# connector_3v3.net
KiCad netlist of a schematic drawn in Altium Designer
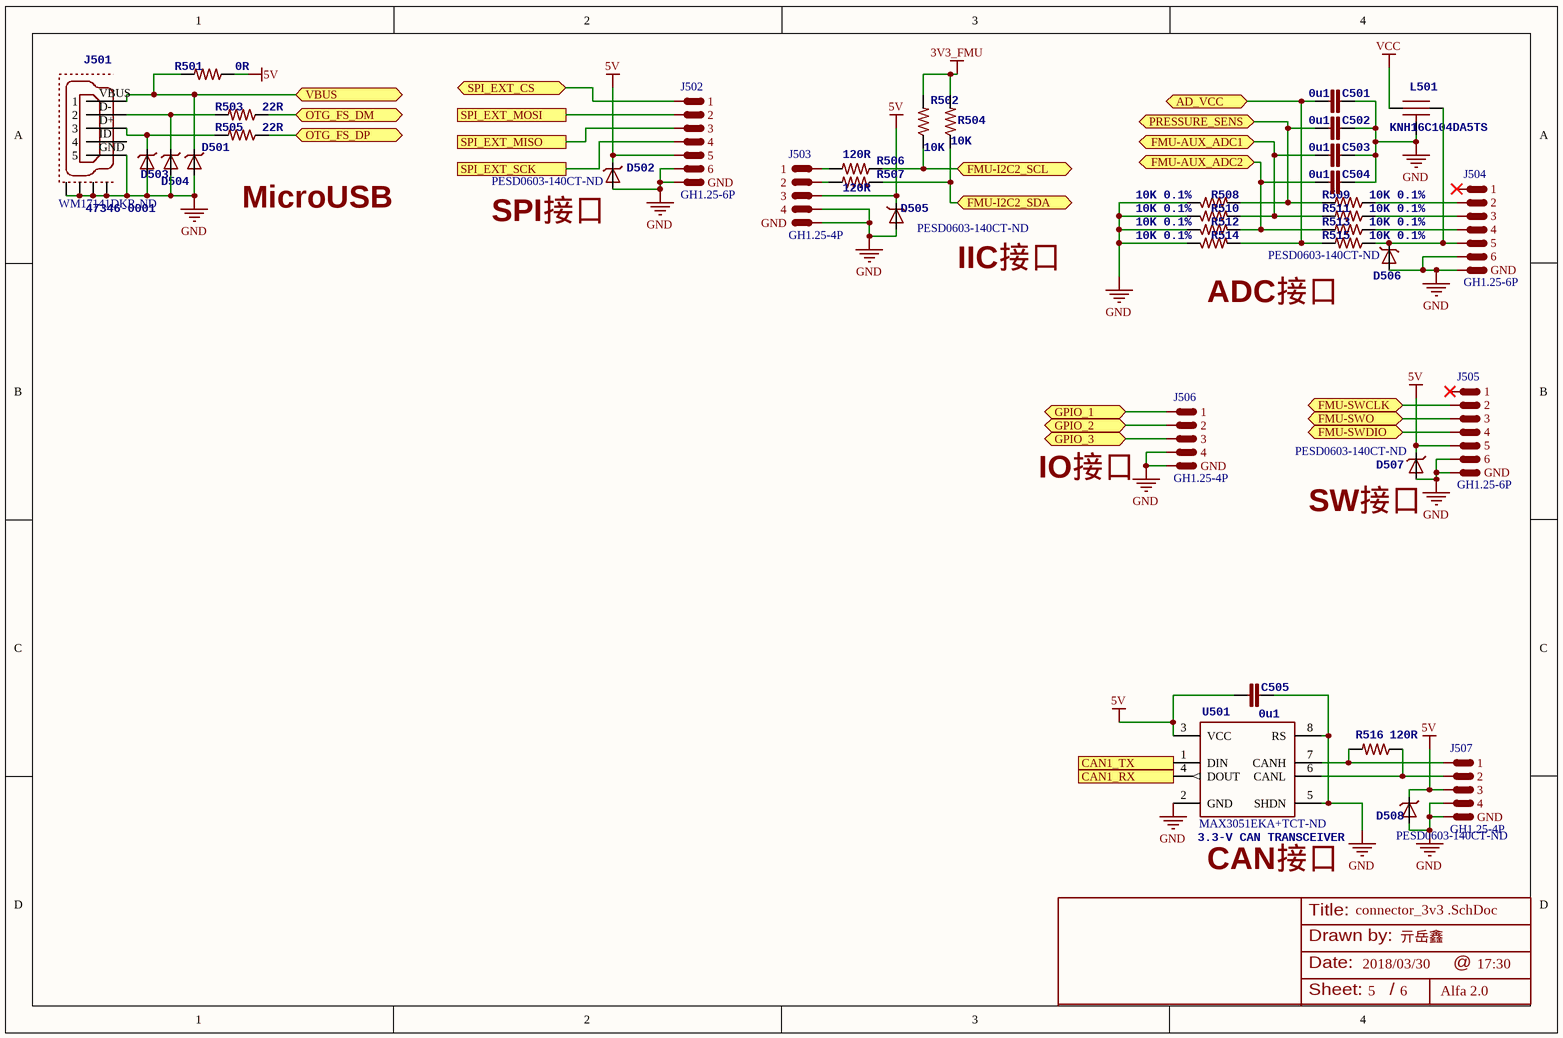
[diagram p0: connector_3v3 .SchDoc]

(export (version "E")
  (design (tool "Eeschema 10.0.6"))
  (components
    (comp (ref "C501")
      (value "0u1")
      (footprint "0603-CAP")
      (description "Capacitor, 0.1uF, 16V, Y5V, 0402, Ceramic")
      (fields (field (name "PARTNO") "CC0402ZRY5V7BB104") (field (name "3DR_PARTNO") "ECM0700"))
      (libsource (lib "Q's无源元件类") (part "CAP0603-0.1uF"))
    )
    (comp (ref "C502")
      (value "0u1")
      (footprint "0603-CAP")
      (description "Capacitor, 0.1uF, 16V, Y5V, 0402, Ceramic")
      (fields (field (name "PARTNO") "CC0402ZRY5V7BB104") (field (name "3DR_PARTNO") "ECM0700"))
      (libsource (lib "Q's无源元件类") (part "CAP0603-0.1uF"))
    )
    (comp (ref "C503")
      (value "0u1")
      (footprint "0603-CAP")
      (description "Capacitor, 0.1uF, 16V, Y5V, 0402, Ceramic")
      (fields (field (name "PARTNO") "CC0402ZRY5V7BB104") (field (name "3DR_PARTNO") "ECM0700"))
      (libsource (lib "Q's无源元件类") (part "CAP0603-0.1uF"))
    )
    (comp (ref "C504")
      (value "0u1")
      (footprint "0603-CAP")
      (description "Capacitor, 0.1uF, 16V, Y5V, 0402, Ceramic")
      (fields (field (name "PARTNO") "CC0402ZRY5V7BB104") (field (name "3DR_PARTNO") "ECM0700"))
      (libsource (lib "Q's无源元件类") (part "CAP0603-0.1uF"))
    )
    (comp (ref "C505")
      (value "0u1")
      (footprint "0603-CAP")
      (description "Capacitor, 0.1uF, 16V, Y5V, 0402, Ceramic")
      (fields (field (name "PARTNO") "CC0402ZRY5V7BB104") (field (name "3DR_PARTNO") "ECM0700"))
      (libsource (lib "Q's无源元件类") (part "CAP0603-0.1uF"))
    )
    (comp (ref "D501")
      (value "PESD0603-140")
      (footprint "0603-ESD")
      (description "TVS DIODE 14V 0603")
      (libsource (lib "Q's无源元件类") (part "DIODE-ESD"))
    )
    (comp (ref "D502")
      (value "PESD0603-140")
      (footprint "0603-ESD")
      (description "TVS DIODE 14V 0603")
      (fields (field (name "SUPPLIER PART NUMBER 1") "PESD0603-140CT-ND"))
      (libsource (lib "Q's无源元件类") (part "DIODE-ESD"))
    )
    (comp (ref "D503")
      (value "PESD0603-140")
      (footprint "0603-ESD")
      (description "TVS DIODE 14V 0603")
      (libsource (lib "Q's无源元件类") (part "DIODE-ESD"))
    )
    (comp (ref "D504")
      (value "PESD0603-140")
      (footprint "0603-ESD")
      (description "TVS DIODE 14V 0603")
      (libsource (lib "Q's无源元件类") (part "DIODE-ESD"))
    )
    (comp (ref "D505")
      (value "PESD0603-140")
      (footprint "0603-ESD")
      (description "TVS DIODE 14V 0603")
      (fields (field (name "SUPPLIER PART NUMBER 1") "PESD0603-140CT-ND"))
      (libsource (lib "Q's无源元件类") (part "DIODE-ESD"))
    )
    (comp (ref "D506")
      (value "PESD0603-140")
      (footprint "0603-ESD")
      (description "TVS DIODE 14V 0603")
      (fields (field (name "SUPPLIER PART NUMBER 1") "PESD0603-140CT-ND"))
      (libsource (lib "Q's无源元件类") (part "DIODE-ESD"))
    )
    (comp (ref "D507")
      (value "PESD0603-140")
      (footprint "0603-ESD")
      (description "TVS DIODE 14V 0603")
      (fields (field (name "SUPPLIER PART NUMBER 1") "PESD0603-140CT-ND"))
      (libsource (lib "Q's无源元件类") (part "DIODE-ESD"))
    )
    (comp (ref "D508")
      (value "PESD0603-140")
      (footprint "0603-ESD")
      (description "TVS DIODE 14V 0603")
      (fields (field (name "SUPPLIER PART NUMBER 1") "PESD0603-140CT-ND"))
      (libsource (lib "Q's无源元件类") (part "DIODE-ESD"))
    )
    (comp (ref "J501")
      (value "47346-0001")
      (footprint "MOLEX-47346-0001")
      (description "MICRO USB B, BOTTOM MOUNT")
      (fields
        (field (name "3DR_PARTNO") "ECM0486")
        (field (name "PARTNO") "0473460001")
        (field (name "SUPPLIER PART NUMBER 1") "WM17141DKR-ND")
      )
      (libsource (lib "Q's端子及图标") (part "MicroUSB"))
    )
    (comp (ref "J502")
      (value "GH1.25-6P")
      (footprint "1.25-6P")
      (description "GH1.25mm 立贴 间距1.25mm 连接器贴片")
      (libsource (lib "Q's端子及图标") (part "GH1.25-6P"))
    )
    (comp (ref "J503")
      (value "GH1.25-4P")
      (footprint "1.25-4P")
      (description "GH1.25mm 立贴 间距1.25mm 连接器贴片")
      (libsource (lib "Q's端子及图标") (part "GH1.25-4P"))
    )
    (comp (ref "J504")
      (value "GH1.25-6P")
      (footprint "1.25-6P")
      (description "GH1.25mm 立贴 间距1.25mm 连接器贴片")
      (libsource (lib "Q's端子及图标") (part "GH1.25-6P"))
    )
    (comp (ref "J505")
      (value "GH1.25-6P")
      (footprint "1.25-6P")
      (description "GH1.25mm 立贴 间距1.25mm 连接器贴片")
      (libsource (lib "Q's端子及图标") (part "GH1.25-6P"))
    )
    (comp (ref "J506")
      (value "GH1.25-4P")
      (footprint "1.25-4P")
      (description "GH1.25mm 立贴 间距1.25mm 连接器贴片")
      (libsource (lib "Q's端子及图标") (part "GH1.25-4P"))
    )
    (comp (ref "J507")
      (value "GH1.25-4P")
      (footprint "1.25-4P")
      (description "GH1.25mm 立贴 间距1.25mm 连接器贴片")
      (libsource (lib "Q's端子及图标") (part "GH1.25-4P"))
    )
    (comp (ref "L501")
      (value "KNH16C104DA5TS")
      (footprint "0603-KNH16-DA")
      (description "EMI FILTER CAP 0.1UF 2A 25V 0603")
      (fields (field (name "3DR_PARTNO") "ECM0719"))
      (libsource (lib "Q's无源元件类") (part "EMI Filters"))
    )
    (comp (ref "R501")
      (value "0R")
      (footprint "0603-RES")
      (description "RES 0R OHM 1/10W 5% 0603")
      (libsource (lib "Q's无源元件类") (part "RES0603-0R"))
    )
    (comp (ref "R502")
      (value "10K")
      (footprint "0603-RES")
      (description "RES 10K OHM 1/10W 5% 0603")
      (libsource (lib "Q's无源元件类") (part "RES0603-10K"))
    )
    (comp (ref "R503")
      (value "22R")
      (footprint "0603-RES")
      (description "RES 22R OHM 1/10W 5% 0603")
      (libsource (lib "Q's无源元件类") (part "RES0603-22R"))
    )
    (comp (ref "R504")
      (value "10K")
      (footprint "0603-RES")
      (description "RES 10K OHM 1/10W 5% 0603")
      (libsource (lib "Q's无源元件类") (part "RES0603-10K"))
    )
    (comp (ref "R505")
      (value "22R")
      (footprint "0603-RES")
      (description "RES 22R OHM 1/10W 5% 0603")
      (libsource (lib "Q's无源元件类") (part "RES0603-22R"))
    )
    (comp (ref "R506")
      (value "120R")
      (footprint "0603-RES")
      (description "RES 120R OHM 1/10W 5% 0603")
      (libsource (lib "Q's无源元件类") (part "RES0603-120R"))
    )
    (comp (ref "R507")
      (value "120R")
      (footprint "0603-RES")
      (description "RES 120R OHM 1/10W 5% 0603")
      (libsource (lib "Q's无源元件类") (part "RES0603-120R"))
    )
    (comp (ref "R508")
      (value "10K 0.1%")
      (footprint "0603-RES")
      (description "RES 10 OHM 1/10W 0.1% 0603")
      (libsource (lib "Q's无源元件类") (part "RES0603-10k_0.1%"))
    )
    (comp (ref "R509")
      (value "10K 0.1%")
      (footprint "0603-RES")
      (description "RES 10 OHM 1/10W 0.1% 0603")
      (libsource (lib "Q's无源元件类") (part "RES0603-10k_0.1%"))
    )
    (comp (ref "R510")
      (value "10K 0.1%")
      (footprint "0603-RES")
      (description "RES 10 OHM 1/10W 0.1% 0603")
      (libsource (lib "Q's无源元件类") (part "RES0603-10k_0.1%"))
    )
    (comp (ref "R511")
      (value "10K 0.1%")
      (footprint "0603-RES")
      (description "RES 10 OHM 1/10W 0.1% 0603")
      (libsource (lib "Q's无源元件类") (part "RES0603-10k_0.1%"))
    )
    (comp (ref "R512")
      (value "10K 0.1%")
      (footprint "0603-RES")
      (description "RES 10 OHM 1/10W 0.1% 0603")
      (libsource (lib "Q's无源元件类") (part "RES0603-10k_0.1%"))
    )
    (comp (ref "R513")
      (value "10K 0.1%")
      (footprint "0603-RES")
      (description "RES 10 OHM 1/10W 0.1% 0603")
      (libsource (lib "Q's无源元件类") (part "RES0603-10k_0.1%"))
    )
    (comp (ref "R514")
      (value "10K 0.1%")
      (footprint "0603-RES")
      (description "RES 10 OHM 1/10W 0.1% 0603")
      (libsource (lib "Q's无源元件类") (part "RES0603-10k_0.1%"))
    )
    (comp (ref "R515")
      (value "10K 0.1%")
      (footprint "0603-RES")
      (description "RES 10 OHM 1/10W 0.1% 0603")
      (libsource (lib "Q's无源元件类") (part "RES0603-10k_0.1%"))
    )
    (comp (ref "R516")
      (value "120R")
      (footprint "0603-RES")
      (description "RES 120R OHM 1/10W 5% 0603")
      (libsource (lib "Q's无源元件类") (part "RES0603-120R"))
    )
    (comp (ref "U501")
      (value "3.3-V CAN TRANSCEIVER")
      (footprint "SOT23-8")
      (description "IC TXRX CAN 1MBPS SOT23-8")
      (fields
        (field (name "3DR_PARTNO") "ECM0831")
        (field (name "PARTNO") "MAX3051EKA+T")
        (field (name "SUPPLIER PART NUMBER 1") "MAX3051EKA+TCT-ND")
      )
      (libsource (lib "Q's有源芯片类") (part "MAX3051"))
    )
  )
  (nets
    (net (code "1") (name "/AD_VCC") (class "Default")
      (node (ref "C501") (pin "P$1") (pinfunction "1_P$1") (pintype "passive"))
      (node (ref "R514") (pin "2") (pinfunction "2_2") (pintype "passive"))
      (node (ref "R515") (pin "2") (pinfunction "2_2") (pintype "passive"))
    )
    (net (code "2") (name "/CAN1_RX") (class "Default")
      (node (ref "U501") (pin "4") (pinfunction "DOUT_4") (pintype "output"))
    )
    (net (code "3") (name "/CAN1_TX") (class "Default")
      (node (ref "U501") (pin "1") (pinfunction "DIN_1") (pintype "passive"))
    )
    (net (code "4") (name "/FMU-AUX_ADC1") (class "Default")
      (node (ref "C503") (pin "P$1") (pinfunction "1_P$1") (pintype "passive"))
      (node (ref "R510") (pin "2") (pinfunction "2_2") (pintype "passive"))
      (node (ref "R511") (pin "2") (pinfunction "2_2") (pintype "passive"))
    )
    (net (code "5") (name "/FMU-AUX_ADC2") (class "Default")
      (node (ref "C504") (pin "P$1") (pinfunction "1_P$1") (pintype "passive"))
      (node (ref "R512") (pin "2") (pinfunction "2_2") (pintype "passive"))
      (node (ref "R513") (pin "2") (pinfunction "2_2") (pintype "passive"))
    )
    (net (code "6") (name "/FMU-I2C2_SCL") (class "Default")
      (node (ref "R502") (pin "1") (pinfunction "1_1") (pintype "passive"))
      (node (ref "R506") (pin "1") (pinfunction "1_1") (pintype "passive"))
    )
    (net (code "7") (name "/FMU-I2C2_SDA") (class "Default")
      (node (ref "R504") (pin "1") (pinfunction "1_1") (pintype "passive"))
      (node (ref "R507") (pin "1") (pinfunction "1_1") (pintype "passive"))
    )
    (net (code "8") (name "/FMU-SWCLK") (class "Default")
      (node (ref "J505") (pin "2") (pinfunction "2_2") (pintype "passive"))
    )
    (net (code "9") (name "/FMU-SWDIO") (class "Default")
      (node (ref "J505") (pin "4") (pinfunction "4_4") (pintype "passive"))
    )
    (net (code "10") (name "/FMU-SWO") (class "Default")
      (node (ref "J505") (pin "3") (pinfunction "3_3") (pintype "passive"))
    )
    (net (code "11") (name "/GPIO_1") (class "Default")
      (node (ref "J506") (pin "1") (pinfunction "1_1") (pintype "passive"))
    )
    (net (code "12") (name "/GPIO_2") (class "Default")
      (node (ref "J506") (pin "2") (pinfunction "2_2") (pintype "passive"))
    )
    (net (code "13") (name "/GPIO_3") (class "Default")
      (node (ref "J506") (pin "3") (pinfunction "3_3") (pintype "passive"))
    )
    (net (code "14") (name "/OTG_FS_DM") (class "Default")
      (node (ref "R503") (pin "1") (pinfunction "1_1") (pintype "passive"))
    )
    (net (code "15") (name "/OTG_FS_DP") (class "Default")
      (node (ref "R505") (pin "1") (pinfunction "1_1") (pintype "passive"))
    )
    (net (code "16") (name "/PRESSURE_SENS") (class "Default")
      (node (ref "C502") (pin "P$1") (pinfunction "1_P$1") (pintype "passive"))
      (node (ref "R508") (pin "2") (pinfunction "2_2") (pintype "passive"))
      (node (ref "R509") (pin "2") (pinfunction "2_2") (pintype "passive"))
    )
    (net (code "17") (name "/SPI_EXT_CS") (class "Default")
      (node (ref "J502") (pin "1") (pinfunction "1_1") (pintype "passive"))
    )
    (net (code "18") (name "/SPI_EXT_MISO") (class "Default")
      (node (ref "J502") (pin "3") (pinfunction "3_3") (pintype "passive"))
    )
    (net (code "19") (name "/SPI_EXT_MOSI") (class "Default")
      (node (ref "J502") (pin "2") (pinfunction "2_2") (pintype "passive"))
    )
    (net (code "20") (name "/SPI_EXT_SCK") (class "Default")
      (node (ref "J502") (pin "4") (pinfunction "4_4") (pintype "passive"))
    )
    (net (code "21") (name "/VBUS") (class "Default")
      (node (ref "D501") (pin "C") (pinfunction "C_C") (pintype "passive"))
      (node (ref "J501") (pin "VBUS") (pinfunction "1_VBUS") (pintype "open_emitter"))
      (node (ref "R501") (pin "2") (pinfunction "2_2") (pintype "passive"))
    )
    (net (code "22") (name "3V3_FMU") (class "Default")
      (node (ref "R502") (pin "2") (pinfunction "2_2") (pintype "passive"))
      (node (ref "R504") (pin "2") (pinfunction "2_2") (pintype "passive"))
    )
    (net (code "23") (name "5V") (class "Default")
      (node (ref "C505") (pin "P$1") (pinfunction "1_P$1") (pintype "passive"))
      (node (ref "D502") (pin "C") (pinfunction "C_C") (pintype "passive"))
      (node (ref "D505") (pin "C") (pinfunction "C_C") (pintype "passive"))
      (node (ref "D507") (pin "C") (pinfunction "C_C") (pintype "passive"))
      (node (ref "D508") (pin "C") (pinfunction "C_C") (pintype "passive"))
      (node (ref "J502") (pin "5") (pinfunction "5_5") (pintype "passive"))
      (node (ref "J503") (pin "3") (pinfunction "3_3") (pintype "passive"))
      (node (ref "J505") (pin "5") (pinfunction "5_5") (pintype "passive"))
      (node (ref "J507") (pin "3") (pinfunction "3_3") (pintype "passive"))
      (node (ref "R501") (pin "1") (pinfunction "1_1") (pintype "passive"))
      (node (ref "U501") (pin "3") (pinfunction "VCC_3") (pintype "passive"))
    )
    (net (code "24") (name "GND") (class "Default")
      (node (ref "C501") (pin "P$2") (pinfunction "2_P$2") (pintype "passive"))
      (node (ref "C502") (pin "P$2") (pinfunction "2_P$2") (pintype "passive"))
      (node (ref "C503") (pin "P$2") (pinfunction "2_P$2") (pintype "passive"))
      (node (ref "C504") (pin "P$2") (pinfunction "2_P$2") (pintype "passive"))
      (node (ref "C505") (pin "P$2") (pinfunction "2_P$2") (pintype "passive"))
      (node (ref "D501") (pin "A") (pinfunction "A_A") (pintype "passive"))
      (node (ref "D502") (pin "A") (pinfunction "A_A") (pintype "passive"))
      (node (ref "D503") (pin "A") (pinfunction "A_A") (pintype "passive"))
      (node (ref "D504") (pin "A") (pinfunction "A_A") (pintype "passive"))
      (node (ref "D505") (pin "A") (pinfunction "A_A") (pintype "passive"))
      (node (ref "D506") (pin "A") (pinfunction "A_A") (pintype "passive"))
      (node (ref "D507") (pin "A") (pinfunction "A_A") (pintype "passive"))
      (node (ref "D508") (pin "A") (pinfunction "A_A") (pintype "passive"))
      (node (ref "J501") (pin "GND") (pinfunction "5_GND") (pintype "passive"))
      (node (ref "J501") (pin "GND1") (pinfunction "GND1_GND1") (pintype "passive"))
      (node (ref "J501") (pin "GND2") (pinfunction "GND2_GND2") (pintype "passive"))
      (node (ref "J501") (pin "GND3") (pinfunction "GND3_GND3") (pintype "passive"))
      (node (ref "J501") (pin "GND4") (pinfunction "GND4_GND4") (pintype "passive"))
      (node (ref "J502") (pin "6") (pinfunction "6_6") (pintype "passive"))
      (node (ref "J502") (pin "GND") (pinfunction "GND_GND") (pintype "passive"))
      (node (ref "J503") (pin "4") (pinfunction "4_4") (pintype "passive"))
      (node (ref "J503") (pin "GND") (pinfunction "GND_GND") (pintype "passive"))
      (node (ref "J504") (pin "6") (pinfunction "6_6") (pintype "passive"))
      (node (ref "J504") (pin "GND") (pinfunction "GND_GND") (pintype "passive"))
      (node (ref "J505") (pin "6") (pinfunction "6_6") (pintype "passive"))
      (node (ref "J505") (pin "GND") (pinfunction "GND_GND") (pintype "passive"))
      (node (ref "J506") (pin "4") (pinfunction "4_4") (pintype "passive"))
      (node (ref "J506") (pin "GND") (pinfunction "GND_GND") (pintype "passive"))
      (node (ref "J507") (pin "4") (pinfunction "4_4") (pintype "passive"))
      (node (ref "J507") (pin "GND") (pinfunction "GND_GND") (pintype "passive"))
      (node (ref "L501") (pin "GND") (pinfunction "GND_GND") (pintype "passive"))
      (node (ref "R508") (pin "1") (pinfunction "1_1") (pintype "passive"))
      (node (ref "R510") (pin "1") (pinfunction "1_1") (pintype "passive"))
      (node (ref "R512") (pin "1") (pinfunction "1_1") (pintype "passive"))
      (node (ref "R514") (pin "1") (pinfunction "1_1") (pintype "passive"))
      (node (ref "U501") (pin "2") (pinfunction "GND_2") (pintype "power_in"))
      (node (ref "U501") (pin "5") (pinfunction "SHDN_5") (pintype "passive"))
      (node (ref "U501") (pin "8") (pinfunction "RS_8") (pintype "passive"))
    )
    (net (code "25") (name "Net-(D506-PadC)") (class "Default")
      (node (ref "D506") (pin "C") (pinfunction "C_C") (pintype "passive"))
      (node (ref "J504") (pin "5") (pinfunction "5_5") (pintype "passive"))
      (node (ref "L501") (pin "P$2") (pinfunction "P$2_P$2") (pintype "passive"))
      (node (ref "R515") (pin "1") (pinfunction "1_1") (pintype "passive"))
    )
    (net (code "26") (name "Net-(J501-2)") (class "Default")
      (node (ref "D504") (pin "C") (pinfunction "C_C") (pintype "passive"))
      (node (ref "J501") (pin "D-") (pinfunction "2_D-") (pintype "passive"))
      (node (ref "R503") (pin "2") (pinfunction "2_2") (pintype "passive"))
    )
    (net (code "27") (name "Net-(J501-3)") (class "Default")
      (node (ref "D503") (pin "C") (pinfunction "C_C") (pintype "passive"))
      (node (ref "J501") (pin "D+") (pinfunction "3_D+") (pintype "passive"))
      (node (ref "R505") (pin "2") (pinfunction "2_2") (pintype "passive"))
    )
    (net (code "28") (name "Net-(J503-Pad1)") (class "Default")
      (node (ref "J503") (pin "1") (pinfunction "1_1") (pintype "passive"))
      (node (ref "R506") (pin "2") (pinfunction "2_2") (pintype "passive"))
    )
    (net (code "29") (name "Net-(J503-Pad2)") (class "Default")
      (node (ref "J503") (pin "2") (pinfunction "2_2") (pintype "passive"))
      (node (ref "R507") (pin "2") (pinfunction "2_2") (pintype "passive"))
    )
    (net (code "30") (name "Net-(J504-Pad2)") (class "Default")
      (node (ref "J504") (pin "2") (pinfunction "2_2") (pintype "passive"))
      (node (ref "R509") (pin "1") (pinfunction "1_1") (pintype "passive"))
    )
    (net (code "31") (name "Net-(J504-Pad3)") (class "Default")
      (node (ref "J504") (pin "3") (pinfunction "3_3") (pintype "passive"))
      (node (ref "R511") (pin "1") (pinfunction "1_1") (pintype "passive"))
    )
    (net (code "32") (name "Net-(J504-Pad4)") (class "Default")
      (node (ref "J504") (pin "4") (pinfunction "4_4") (pintype "passive"))
      (node (ref "R513") (pin "1") (pinfunction "1_1") (pintype "passive"))
    )
    (net (code "33") (name "Net-(U501-CANH)") (class "Default")
      (node (ref "J507") (pin "1") (pinfunction "1_1") (pintype "passive"))
      (node (ref "R516") (pin "2") (pinfunction "2_2") (pintype "passive"))
      (node (ref "U501") (pin "7") (pinfunction "CANH_7") (pintype "passive"))
    )
    (net (code "34") (name "Net-(U501-CANL)") (class "Default")
      (node (ref "J507") (pin "2") (pinfunction "2_2") (pintype "passive"))
      (node (ref "R516") (pin "1") (pinfunction "1_1") (pintype "passive"))
      (node (ref "U501") (pin "6") (pinfunction "CANL_6") (pintype "passive"))
    )
    (net (code "35") (name "VCC") (class "Default")
      (node (ref "L501") (pin "P$1") (pinfunction "P$1_P$1") (pintype "passive"))
    )
    (net (code "36") (name "unconnected-(J501-4-PadID)") (class "Default")
      (node (ref "J501") (pin "ID") (pinfunction "4_ID") (pintype "passive"))
    )
    (net (code "37") (name "unconnected-(J504-Pad1)") (class "Default")
      (node (ref "J504") (pin "1") (pinfunction "1_1") (pintype "passive+no_connect"))
    )
    (net (code "38") (name "unconnected-(J505-Pad1)") (class "Default")
      (node (ref "J505") (pin "1") (pinfunction "1_1") (pintype "passive+no_connect"))
    )
  )
)
